# 24VRegulator.net
KiCad netlist of a schematic drawn in Altium Designer
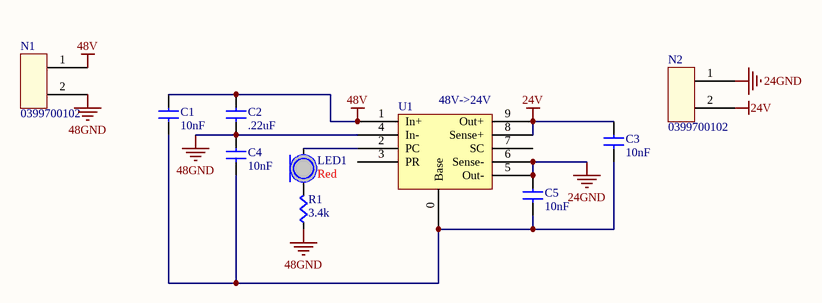
[diagram p0: 24VRegulator.SchDoc]

(export (version "E")
  (design (tool "Eeschema 10.0.6"))
  (components
    (comp (ref "C1")
      (value "10nF")
      (footprint "CAP2225")
      (fields (field (name "Comment") "Cap"))
      (libsource (lib "SubjuGator8") (part "Cap"))
    )
    (comp (ref "C2")
      (value ".22uF")
      (footprint "CAP2225")
      (fields (field (name "Comment") "Cap"))
      (libsource (lib "SubjuGator8") (part "Cap"))
    )
    (comp (ref "C3")
      (value "10nF")
      (footprint "CAP2225")
      (fields (field (name "Comment") "Cap"))
      (libsource (lib "SubjuGator8") (part "Cap"))
    )
    (comp (ref "C4")
      (value "10nF")
      (footprint "CAP2225")
      (fields (field (name "Comment") "Cap"))
      (libsource (lib "SubjuGator8") (part "Cap"))
    )
    (comp (ref "C5")
      (value "10nF")
      (footprint "CAP2225")
      (fields (field (name "Comment") "Cap"))
      (libsource (lib "SubjuGator8") (part "Cap"))
    )
    (comp (ref "LED1")
      (value "LED")
      (footprint "LED0603")
      (fields (field (name "COLOR") "Red"))
      (libsource (lib "SubjuGator8") (part "LED"))
    )
    (comp (ref "N1")
      (value "0399700102")
      (footprint "MOLEX-TERMINAL-1x2-EUROSTYLE-60A")
      (description "Giant 60A two position screw terminal")
      (libsource (lib "Connectors") (part "MOLEX-TERMINAL-1x2-EUROSTYLE-60A"))
    )
    (comp (ref "N2")
      (value "0399700102")
      (footprint "MOLEX-TERMINAL-1x2-EUROSTYLE-60A_Reversed")
      (description "Giant 60A two position screw terminal")
      (libsource (lib "Connectors") (part "MOLEX-TERMINAL-1x2-EUROSTYLE-60A"))
    )
    (comp (ref "R1")
      (value "3.4k")
      (footprint "RES0603")
      (fields (field (name "Comment") "Res"))
      (libsource (lib "SubjuGator8") (part "Res"))
    )
    (comp (ref "U1")
      (value "48V->24V")
      (footprint "FASTRAK_MINI_ONBOARD_MOUNT")
      (description "CONVERTER MOD DC/DC 24V 250W")
      (libsource (lib "SubjuGator8") (part "V48B24C250BL"))
    )
  )
  (nets
    (net (code "1") (name "24GND") (class "Default")
      (node (ref "C5") (pin "1") (pinfunction "A_1") (pintype "passive"))
      (node (ref "N2") (pin "1") (pinfunction "1_1") (pintype "passive"))
      (node (ref "U1") (pin "5") (pinfunction "Out-_5") (pintype "passive"))
      (node (ref "U1") (pin "6") (pinfunction "Sense-_6") (pintype "passive"))
    )
    (net (code "2") (name "24V") (class "Default")
      (node (ref "C3") (pin "1") (pinfunction "A_1") (pintype "passive"))
      (node (ref "N2") (pin "2") (pinfunction "2_2") (pintype "passive"))
      (node (ref "U1") (pin "8") (pinfunction "Sense+_8") (pintype "passive"))
      (node (ref "U1") (pin "9") (pinfunction "Out+_9") (pintype "passive"))
    )
    (net (code "3") (name "48GND") (class "Default")
      (node (ref "C2") (pin "2") (pinfunction "B_2") (pintype "passive"))
      (node (ref "C4") (pin "1") (pinfunction "A_1") (pintype "passive"))
      (node (ref "N1") (pin "2") (pinfunction "2_2") (pintype "passive"))
      (node (ref "R1") (pin "2") (pinfunction "B_2") (pintype "passive"))
      (node (ref "U1") (pin "4") (pinfunction "In-_4") (pintype "passive"))
    )
    (net (code "4") (name "48V") (class "Default")
      (node (ref "C1") (pin "1") (pinfunction "A_1") (pintype "passive"))
      (node (ref "C2") (pin "1") (pinfunction "A_1") (pintype "passive"))
      (node (ref "N1") (pin "1") (pinfunction "1_1") (pintype "passive"))
      (node (ref "U1") (pin "1") (pinfunction "In+_1") (pintype "passive"))
    )
    (net (code "5") (name "Net-(C1-B)") (class "Default")
      (node (ref "C1") (pin "2") (pinfunction "B_2") (pintype "passive"))
      (node (ref "C3") (pin "2") (pinfunction "B_2") (pintype "passive"))
      (node (ref "C4") (pin "2") (pinfunction "B_2") (pintype "passive"))
      (node (ref "C5") (pin "2") (pinfunction "B_2") (pintype "passive"))
      (node (ref "U1") (pin "0") (pinfunction "Base_0") (pintype "passive"))
    )
    (net (code "6") (name "Net-(R1-A)") (class "Default")
      (node (ref "LED1") (pin "C") (pinfunction "C_C") (pintype "passive"))
      (node (ref "R1") (pin "1") (pinfunction "A_1") (pintype "passive"))
    )
    (net (code "7") (name "Net-(U1-PC)") (class "Default")
      (node (ref "LED1") (pin "A") (pinfunction "A_A") (pintype "passive"))
      (node (ref "U1") (pin "2") (pinfunction "PC_2") (pintype "passive"))
    )
    (net (code "8") (name "unconnected-(U1-PR-Pad3)") (class "Default")
      (node (ref "U1") (pin "3") (pinfunction "PR_3") (pintype "passive"))
    )
    (net (code "9") (name "unconnected-(U1-SC-Pad7)") (class "Default")
      (node (ref "U1") (pin "7") (pinfunction "SC_7") (pintype "passive"))
    )
  )
)
